# PowerBoardSchematicV2.net
KiCad netlist of a schematic drawn in Altium Designer
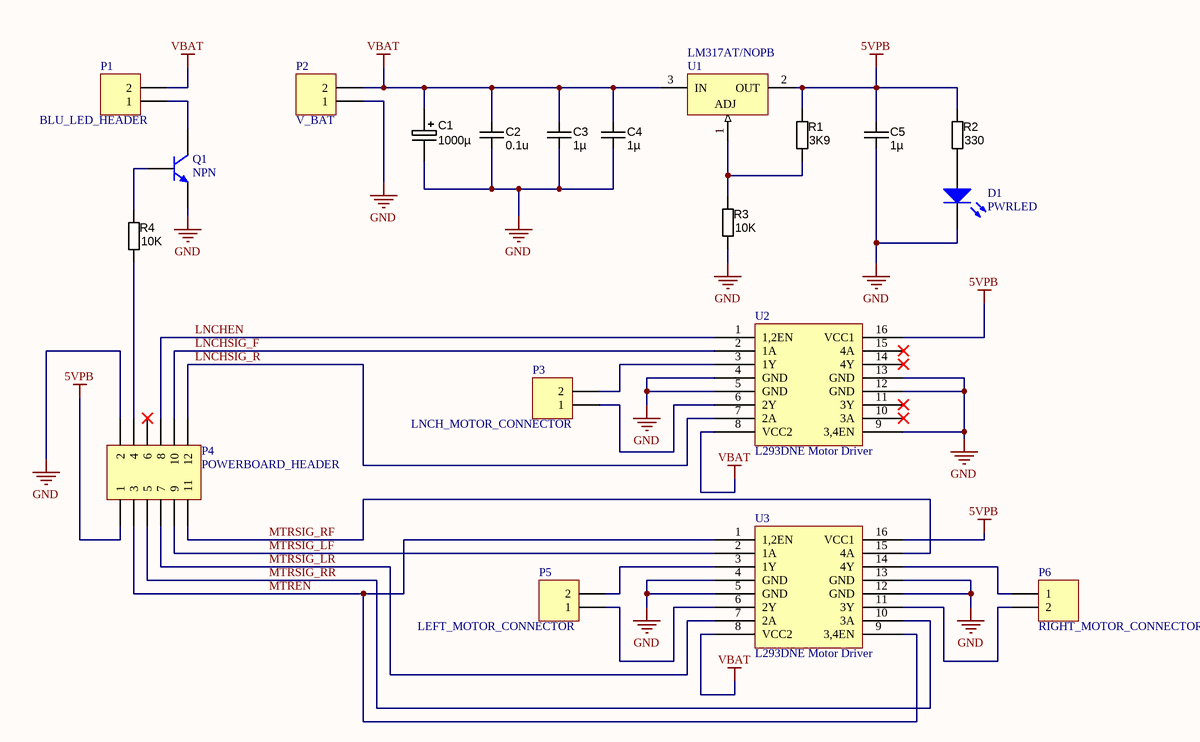
[diagram p0: PowerBoardSchematicV2.SchDoc]

(export (version "E")
  (design (tool "Eeschema 10.0.6"))
  (components
    (comp (ref "C1")
      (value "1000µ")
      (footprint "CAPE5.0mm")
      (description "Capacitor THT Alum Elec 33uF 20% 200V")
      (fields (field (name "TOLERANCE") "±20%"))
      (libsource (lib "PBL - Capacitors") (part "CAPE_33u_200V_THT"))
    )
    (comp (ref "C2")
      (value "0.1u")
      (footprint "CAPC2012X135N")
      (description "Capacitor SMD Cer 1.8nF 10% 50V X7R 0805")
      (fields (field (name "TOLERANCE") "±10%") (field (name "Comment") "approved sub OK"))
      (libsource (lib "PBL - Capacitors") (part "CAPC_1n8_50V_0805"))
    )
    (comp (ref "C3")
      (value "1µ")
      (footprint "CAPC3216X180N")
      (description "Capacitor SMD Cer 10uF 10% 16V X7R 1206")
      (fields (field (name "TOLERANCE") "±10%") (field (name "Comment") "approved sub OK"))
      (libsource (lib "PBL - Capacitors") (part "CAPC_10u_1206_16V"))
    )
    (comp (ref "C4")
      (value "1µ")
      (footprint "CAPC3216X180N")
      (description "Capacitor SMD Cer 10uF 10% 16V X7R 1206")
      (fields (field (name "TOLERANCE") "±10%") (field (name "Comment") "approved sub OK"))
      (libsource (lib "PBL - Capacitors") (part "CAPC_10u_1206_16V"))
    )
    (comp (ref "C5")
      (value "1µ")
      (footprint "CAPC3216X180N")
      (description "Capacitor SMD Cer 10uF 10% 16V X7R 1206")
      (fields (field (name "TOLERANCE") "±10%") (field (name "Comment") "approved sub OK"))
      (libsource (lib "PBL - Capacitors") (part "CAPC_10u_1206_16V"))
    )
    (comp (ref "D1")
      (value "PWRLED")
      (footprint "3.5X2.8X1.9")
      (description "Typical BLUE SiC LED")
      (fields (field (name "PUBLISHER") "Altium Limited"))
      (libsource (lib "Miscellaneous Devices") (part "LED3"))
    )
    (comp (ref "P1")
      (value "BLU_LED_HEADER")
      (footprint "HDR1X2")
      (description "Header, 2-Pin")
      (fields (field (name "PUBLISHER") "Altium Limited"))
      (libsource (lib "Miscellaneous Connectors") (part "Header 2"))
    )
    (comp (ref "P2")
      (value "V_BAT")
      (footprint "HDR1X2")
      (description "Header, 2-Pin")
      (fields (field (name "PUBLISHER") "Altium Limited"))
      (libsource (lib "Miscellaneous Connectors") (part "Header 2"))
    )
    (comp (ref "P3")
      (value "LNCH_MOTOR_CONNECTOR")
      (footprint "HDR1X2")
      (description "Header, 2-Pin")
      (fields (field (name "PUBLISHER") "Altium Limited"))
      (libsource (lib "Miscellaneous Connectors") (part "Header 2"))
    )
    (comp (ref "P4")
      (value "POWERBOARD_HEADER")
      (footprint "HDR2X6")
      (description "Header, 6-Pin, Dual row")
      (fields (field (name "PUBLISHER") "Altium Limited"))
      (libsource (lib "Miscellaneous Connectors") (part "Header 6X2"))
    )
    (comp (ref "P5")
      (value "LEFT_MOTOR_CONNECTOR")
      (footprint "HDR1X2")
      (description "Header, 2-Pin")
      (fields (field (name "PUBLISHER") "Altium Limited"))
      (libsource (lib "Miscellaneous Connectors") (part "Header 2"))
    )
    (comp (ref "P6")
      (value "RIGHT_MOTOR_CONNECTOR")
      (footprint "HDR1X2")
      (description "Header, 2-Pin")
      (fields (field (name "PUBLISHER") "Altium Limited"))
      (libsource (lib "") (part "Header 2_1"))
    )
    (comp (ref "Q1")
      (value "NPN")
      (footprint "TO-226-AA")
      (description "NPN Bipolar Transistor")
      (fields (field (name "PUBLISHER") "Altium Limited"))
      (libsource (lib "Miscellaneous Devices") (part "NPN"))
    )
    (comp (ref "R1")
      (value "3K9")
      (footprint "RESC2012X70N")
      (description "Resistor SMD chip 10k Ohm 0.125W 5% 0805")
      (fields (field (name "TOLERANCE") "±5%"))
      (libsource (lib "PBL - Resistors") (part "RES_10K_0805_5%"))
    )
    (comp (ref "R2")
      (value "330")
      (footprint "RESC2012X70N")
      (description "Resistor SMD chip 10k Ohm 0.125W 5% 0805")
      (fields (field (name "TOLERANCE") "±5%"))
      (libsource (lib "PBL - Resistors") (part "RES_10K_0805_5%"))
    )
    (comp (ref "R3")
      (value "10K")
      (footprint "RESC2012X70N")
      (description "Resistor SMD chip 10k Ohm 0.125W 5% 0805")
      (fields (field (name "TOLERANCE") "±5%"))
      (libsource (lib "PBL - Resistors") (part "RES_10K_0805_5%"))
    )
    (comp (ref "R4")
      (value "10K")
      (footprint "RESC2012N_ZERO")
      (description "Resistor SMD chip 0.0 Ohm 0.125W 0805")
      (libsource (lib "PBL - Resistors") (part "RES_0R_0805"))
    )
    (comp (ref "U1")
      (value "LM317AT/NOPB")
      (footprint "T03B")
      (description "3-Terminal Adjustable Regulator, 3-pin TO-220, Pb-Free")
      (fields (field (name "MANUFACTURER") "National Semiconductor"))
      (libsource (lib "Altium Content Vault") (part "PM-REG-LM1086ADJ-SIL3"))
    )
    (comp (ref "U2")
      (value "L293DNE Motor Driver")
      (footprint "DIP16 (NE)")
      (description "TI L293DNE Quad H-bridge Motor Driver")
      (libsource (lib "L293DNE") (part "L293DNE"))
    )
    (comp (ref "U3")
      (value "L293DNE Motor Driver")
      (footprint "DIP16 (NE)")
      (description "TI L293DNE Quad H-bridge Motor Driver")
      (libsource (lib "L293DNE") (part "L293DNE"))
    )
  )
  (nets
    (net (code "1") (name "/LNCHEN") (class "Default")
      (node (ref "P4") (pin "8") (pinfunction "8_8") (pintype "passive"))
      (node (ref "U2") (pin "1") (pinfunction "1,2EN_1") (pintype "passive"))
    )
    (net (code "2") (name "/LNCHSIG_F") (class "Default")
      (node (ref "P4") (pin "10") (pinfunction "10_10") (pintype "passive"))
      (node (ref "U2") (pin "2") (pinfunction "1A_2") (pintype "passive"))
    )
    (net (code "3") (name "/LNCHSIG_R") (class "Default")
      (node (ref "P4") (pin "12") (pinfunction "12_12") (pintype "passive"))
      (node (ref "U2") (pin "7") (pinfunction "2A_7") (pintype "passive"))
    )
    (net (code "4") (name "/MTREN") (class "Default")
      (node (ref "P4") (pin "3") (pinfunction "3_3") (pintype "passive"))
      (node (ref "U3") (pin "1") (pinfunction "1,2EN_1") (pintype "passive"))
      (node (ref "U3") (pin "9") (pinfunction "3,4EN_9") (pintype "passive"))
    )
    (net (code "5") (name "/MTRSIG_LF") (class "Default")
      (node (ref "P4") (pin "9") (pinfunction "9_9") (pintype "passive"))
      (node (ref "U3") (pin "2") (pinfunction "1A_2") (pintype "passive"))
    )
    (net (code "6") (name "/MTRSIG_LR") (class "Default")
      (node (ref "P4") (pin "7") (pinfunction "7_7") (pintype "passive"))
      (node (ref "U3") (pin "7") (pinfunction "2A_7") (pintype "passive"))
    )
    (net (code "7") (name "/MTRSIG_RF") (class "Default")
      (node (ref "P4") (pin "11") (pinfunction "11_11") (pintype "passive"))
      (node (ref "U3") (pin "15") (pinfunction "4A_15") (pintype "passive"))
    )
    (net (code "8") (name "/MTRSIG_RR") (class "Default")
      (node (ref "P4") (pin "5") (pinfunction "5_5") (pintype "passive"))
      (node (ref "U3") (pin "10") (pinfunction "3A_10") (pintype "passive"))
    )
    (net (code "9") (name "5VPB") (class "Default")
      (node (ref "C5") (pin "1") (pintype "passive"))
      (node (ref "P4") (pin "1") (pinfunction "1_1") (pintype "passive"))
      (node (ref "R1") (pin "1") (pinfunction "1_1") (pintype "passive"))
      (node (ref "R2") (pin "1") (pinfunction "1_1") (pintype "passive"))
      (node (ref "U1") (pin "2") (pinfunction "OUT_2") (pintype "power_in"))
      (node (ref "U2") (pin "16") (pinfunction "VCC1_16") (pintype "passive"))
      (node (ref "U3") (pin "16") (pinfunction "VCC1_16") (pintype "passive"))
    )
    (net (code "10") (name "GND") (class "Default")
      (node (ref "C1") (pin "2") (pintype "passive"))
      (node (ref "C2") (pin "2") (pintype "passive"))
      (node (ref "C3") (pin "2") (pintype "passive"))
      (node (ref "C4") (pin "2") (pintype "passive"))
      (node (ref "C5") (pin "2") (pintype "passive"))
      (node (ref "D1") (pin "2") (pinfunction "K_2") (pintype "passive"))
      (node (ref "P2") (pin "1") (pinfunction "1_1") (pintype "passive"))
      (node (ref "P4") (pin "2") (pinfunction "2_2") (pintype "passive"))
      (node (ref "Q1") (pin "3") (pinfunction "E_3") (pintype "passive"))
      (node (ref "R3") (pin "2") (pinfunction "2_2") (pintype "passive"))
      (node (ref "U2") (pin "12") (pinfunction "GND_12") (pintype "passive"))
      (node (ref "U2") (pin "13") (pinfunction "GND_13") (pintype "passive"))
      (node (ref "U2") (pin "4") (pinfunction "GND_4") (pintype "passive"))
      (node (ref "U2") (pin "5") (pinfunction "GND_5") (pintype "passive"))
      (node (ref "U2") (pin "9") (pinfunction "3,4EN_9") (pintype "passive"))
      (node (ref "U3") (pin "12") (pinfunction "GND_12") (pintype "passive"))
      (node (ref "U3") (pin "13") (pinfunction "GND_13") (pintype "passive"))
      (node (ref "U3") (pin "4") (pinfunction "GND_4") (pintype "passive"))
      (node (ref "U3") (pin "5") (pinfunction "GND_5") (pintype "passive"))
    )
    (net (code "11") (name "Net-(D1-A)") (class "Default")
      (node (ref "D1") (pin "1") (pinfunction "A_1") (pintype "passive"))
      (node (ref "R2") (pin "2") (pinfunction "2_2") (pintype "passive"))
    )
    (net (code "12") (name "Net-(P4-Pad4)") (class "Default")
      (node (ref "P4") (pin "4") (pinfunction "4_4") (pintype "passive"))
      (node (ref "R4") (pin "2") (pinfunction "2_2") (pintype "passive"))
    )
    (net (code "13") (name "Net-(Q1-B)") (class "Default")
      (node (ref "Q1") (pin "2") (pinfunction "B_2") (pintype "passive"))
      (node (ref "R4") (pin "1") (pinfunction "1_1") (pintype "passive"))
    )
    (net (code "14") (name "Net-(Q1-C)") (class "Default")
      (node (ref "P1") (pin "1") (pinfunction "1_1") (pintype "passive"))
      (node (ref "Q1") (pin "1") (pinfunction "C_1") (pintype "passive"))
    )
    (net (code "15") (name "Net-(U1-ADJ)") (class "Default")
      (node (ref "R1") (pin "2") (pinfunction "2_2") (pintype "passive"))
      (node (ref "R3") (pin "1") (pinfunction "1_1") (pintype "passive"))
      (node (ref "U1") (pin "1") (pinfunction "ADJ_1") (pintype "input"))
    )
    (net (code "16") (name "Net-(U2-1Y)") (class "Default")
      (node (ref "P3") (pin "2") (pinfunction "2_2") (pintype "passive"))
      (node (ref "U2") (pin "3") (pinfunction "1Y_3") (pintype "passive"))
    )
    (net (code "17") (name "Net-(U2-2Y)") (class "Default")
      (node (ref "P3") (pin "1") (pinfunction "1_1") (pintype "passive"))
      (node (ref "U2") (pin "6") (pinfunction "2Y_6") (pintype "passive"))
    )
    (net (code "18") (name "Net-(U3-1Y)") (class "Default")
      (node (ref "P5") (pin "2") (pinfunction "2_2") (pintype "passive"))
      (node (ref "U3") (pin "3") (pinfunction "1Y_3") (pintype "passive"))
    )
    (net (code "19") (name "Net-(U3-2Y)") (class "Default")
      (node (ref "P5") (pin "1") (pinfunction "1_1") (pintype "passive"))
      (node (ref "U3") (pin "6") (pinfunction "2Y_6") (pintype "passive"))
    )
    (net (code "20") (name "Net-(U3-3Y)") (class "Default")
      (node (ref "P6") (pin "2") (pinfunction "2_2") (pintype "passive"))
      (node (ref "U3") (pin "11") (pinfunction "3Y_11") (pintype "passive"))
    )
    (net (code "21") (name "Net-(U3-4Y)") (class "Default")
      (node (ref "P6") (pin "1") (pinfunction "1_1") (pintype "passive"))
      (node (ref "U3") (pin "14") (pinfunction "4Y_14") (pintype "passive"))
    )
    (net (code "22") (name "VBAT") (class "Default")
      (node (ref "C1") (pin "1") (pintype "passive"))
      (node (ref "C2") (pin "1") (pintype "passive"))
      (node (ref "C3") (pin "1") (pintype "passive"))
      (node (ref "C4") (pin "1") (pintype "passive"))
      (node (ref "P1") (pin "2") (pinfunction "2_2") (pintype "passive"))
      (node (ref "P2") (pin "2") (pinfunction "2_2") (pintype "passive"))
      (node (ref "U1") (pin "3") (pinfunction "IN_3") (pintype "power_in"))
      (node (ref "U2") (pin "8") (pinfunction "VCC2_8") (pintype "passive"))
      (node (ref "U3") (pin "8") (pinfunction "VCC2_8") (pintype "passive"))
    )
    (net (code "23") (name "unconnected-(P4-Pad6)") (class "Default")
      (node (ref "P4") (pin "6") (pinfunction "6_6") (pintype "passive+no_connect"))
    )
    (net (code "24") (name "unconnected-(U2-3A-Pad10)") (class "Default")
      (node (ref "U2") (pin "10") (pinfunction "3A_10") (pintype "passive+no_connect"))
    )
    (net (code "25") (name "unconnected-(U2-3Y-Pad11)") (class "Default")
      (node (ref "U2") (pin "11") (pinfunction "3Y_11") (pintype "passive+no_connect"))
    )
    (net (code "26") (name "unconnected-(U2-4A-Pad15)") (class "Default")
      (node (ref "U2") (pin "15") (pinfunction "4A_15") (pintype "passive+no_connect"))
    )
    (net (code "27") (name "unconnected-(U2-4Y-Pad14)") (class "Default")
      (node (ref "U2") (pin "14") (pinfunction "4Y_14") (pintype "passive+no_connect"))
    )
  )
)
